# Guide_laser.net
KiCad netlist of a schematic drawn in Altium Designer
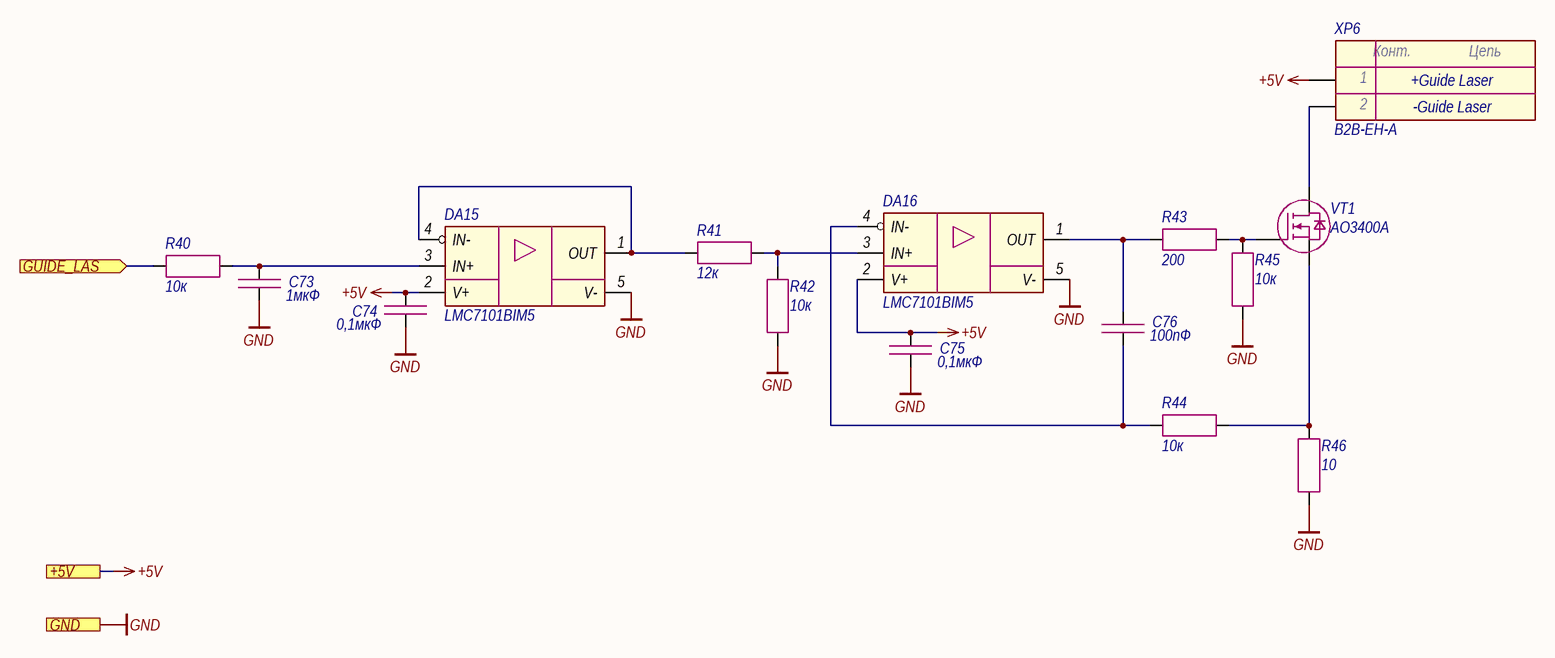
[diagram p0: Guide_laser.SchDoc]

(export (version "E")
  (design (tool "Eeschema 10.0.6"))
  (components
    (comp (ref "C73")
      (value "1мкФ")
      (footprint "Pcb_library:CAP_0603")
      (fields (field (name "MANUFACTURER") "Murata"))
      (libsource (lib "Schem_library") (part "Capacitor"))
    )
    (comp (ref "C74")
      (value "0,1мкФ")
      (footprint "Pcb_library:CAP_0603")
      (fields (field (name "MANUFACTURER") "Murata"))
      (libsource (lib "Schem_library") (part "Capacitor"))
    )
    (comp (ref "C75")
      (value "0,1мкФ")
      (footprint "Pcb_library:CAP_0603")
      (fields (field (name "MANUFACTURER") "Murata"))
      (libsource (lib "Schem_library") (part "Capacitor"))
    )
    (comp (ref "C76")
      (value "100пФ")
      (footprint "Pcb_library:CAP_0603")
      (fields (field (name "MANUFACTURER") "Murata"))
      (libsource (lib "Schem_library") (part "Capacitor"))
    )
    (comp (ref "DA15")
      (value "LMC7101BIM5")
      (footprint "Pcb_library:SOT-23-5")
      (fields (field (name "MANUFACTURER") "Texas Instruments"))
      (libsource (lib "Schem_library") (part "LMC7101"))
    )
    (comp (ref "DA16")
      (value "LMC7101BIM5")
      (footprint "Pcb_library:SOT-23-5")
      (fields (field (name "MANUFACTURER") "Texas Instruments"))
      (libsource (lib "Schem_library") (part "LMC7101"))
    )
    (comp (ref "R40")
      (value "10к")
      (footprint "Pcb_library:RES_0603")
      (fields (field (name "MANUFACTURER") "Yageo"))
      (libsource (lib "Schem_library") (part "Resistor"))
    )
    (comp (ref "R41")
      (value "12к")
      (footprint "Pcb_library:RES_0603")
      (fields (field (name "MANUFACTURER") "Yageo"))
      (libsource (lib "Schem_library") (part "Resistor"))
    )
    (comp (ref "R42")
      (value "10к")
      (footprint "Pcb_library:RES_0603")
      (fields (field (name "MANUFACTURER") "Yageo"))
      (libsource (lib "Schem_library") (part "Resistor"))
    )
    (comp (ref "R43")
      (value "200")
      (footprint "Pcb_library:RES_0603")
      (fields (field (name "MANUFACTURER") "Yageo"))
      (libsource (lib "Schem_library") (part "Resistor"))
    )
    (comp (ref "R44")
      (value "10к")
      (footprint "Pcb_library:RES_0603")
      (fields (field (name "MANUFACTURER") "Yageo"))
      (libsource (lib "Schem_library") (part "Resistor"))
    )
    (comp (ref "R45")
      (value "10к")
      (footprint "Pcb_library:RES_0603")
      (fields (field (name "MANUFACTURER") "Yageo"))
      (libsource (lib "Schem_library") (part "Resistor"))
    )
    (comp (ref "R46")
      (value "10")
      (footprint "Pcb_library:RES_1210")
      (fields (field (name "MANUFACTURER") "Yageo"))
      (libsource (lib "Schem_library") (part "Resistor"))
    )
    (comp (ref "VT1")
      (value "AO3400A")
      (footprint "Pcb_library:SOT-23-3")
      (fields (field (name "MANUFACTURER") "UMW"))
      (libsource (lib "Schem_library") (part "MOSFET N-channel"))
    )
    (comp (ref "XP6")
      (value "B2B-EH-A")
      (footprint "Pcb_library:B2B-EH-A")
      (fields (field (name "MANUFACTURER") "JST"))
      (libsource (lib "Schem_library") (part "Connector-2"))
    )
  )
  (nets
    (net (code "1") (name "+5V") (class "Default")
      (node (ref "C74") (pin "1") (pinfunction "1_1") (pintype "passive"))
      (node (ref "C75") (pin "1") (pinfunction "1_1") (pintype "passive"))
      (node (ref "DA15") (pin "2") (pinfunction "V+_2") (pintype "passive"))
      (node (ref "DA16") (pin "2") (pinfunction "V+_2") (pintype "passive"))
      (node (ref "XP6") (pin "1") (pintype "passive"))
    )
    (net (code "2") (name "/GUIDE_LAS") (class "Default")
      (node (ref "R40") (pin "1") (pinfunction "1_1") (pintype "passive"))
    )
    (net (code "3") (name "GND") (class "Default")
      (node (ref "C73") (pin "2") (pinfunction "2_2") (pintype "passive"))
      (node (ref "C74") (pin "2") (pinfunction "2_2") (pintype "passive"))
      (node (ref "C75") (pin "2") (pinfunction "2_2") (pintype "passive"))
      (node (ref "DA15") (pin "5") (pinfunction "V-_5") (pintype "passive"))
      (node (ref "DA16") (pin "5") (pinfunction "V-_5") (pintype "passive"))
      (node (ref "R42") (pin "2") (pinfunction "2_2") (pintype "passive"))
      (node (ref "R45") (pin "1") (pinfunction "1_1") (pintype "passive"))
      (node (ref "R46") (pin "1") (pinfunction "1_1") (pintype "passive"))
    )
    (net (code "4") (name "Net-(DA15-IN+)") (class "Default")
      (node (ref "C73") (pin "1") (pinfunction "1_1") (pintype "passive"))
      (node (ref "DA15") (pin "3") (pinfunction "IN+_3") (pintype "passive"))
      (node (ref "R40") (pin "2") (pinfunction "2_2") (pintype "passive"))
    )
    (net (code "5") (name "Net-(DA15-IN-)") (class "Default")
      (node (ref "DA15") (pin "1") (pinfunction "OUT_1") (pintype "passive"))
      (node (ref "DA15") (pin "4") (pinfunction "IN-_4") (pintype "passive"))
      (node (ref "R41") (pin "1") (pinfunction "1_1") (pintype "passive"))
    )
    (net (code "6") (name "Net-(DA16-IN+)") (class "Default")
      (node (ref "DA16") (pin "3") (pinfunction "IN+_3") (pintype "passive"))
      (node (ref "R41") (pin "2") (pinfunction "2_2") (pintype "passive"))
      (node (ref "R42") (pin "1") (pinfunction "1_1") (pintype "passive"))
    )
    (net (code "7") (name "Net-(DA16-IN-)") (class "Default")
      (node (ref "C76") (pin "2") (pinfunction "2_2") (pintype "passive"))
      (node (ref "DA16") (pin "4") (pinfunction "IN-_4") (pintype "passive"))
      (node (ref "R44") (pin "1") (pinfunction "1_1") (pintype "passive"))
    )
    (net (code "8") (name "Net-(DA16-OUT)") (class "Default")
      (node (ref "C76") (pin "1") (pinfunction "1_1") (pintype "passive"))
      (node (ref "DA16") (pin "1") (pinfunction "OUT_1") (pintype "passive"))
      (node (ref "R43") (pin "1") (pinfunction "1_1") (pintype "passive"))
    )
    (net (code "9") (name "Net-(VT1-D)") (class "Default")
      (node (ref "VT1") (pin "3") (pinfunction "D_3") (pintype "passive"))
      (node (ref "XP6") (pin "2") (pintype "passive"))
    )
    (net (code "10") (name "Net-(VT1-G)") (class "Default")
      (node (ref "R43") (pin "2") (pinfunction "2_2") (pintype "passive"))
      (node (ref "R45") (pin "2") (pinfunction "2_2") (pintype "passive"))
      (node (ref "VT1") (pin "1") (pinfunction "G_1") (pintype "passive"))
    )
    (net (code "11") (name "Net-(VT1-S)") (class "Default")
      (node (ref "R44") (pin "2") (pinfunction "2_2") (pintype "passive"))
      (node (ref "R46") (pin "2") (pinfunction "2_2") (pintype "passive"))
      (node (ref "VT1") (pin "2") (pinfunction "S_2") (pintype "passive"))
    )
  )
)
